# MainBoard.net
KiCad netlist of a schematic drawn in Altium Designer
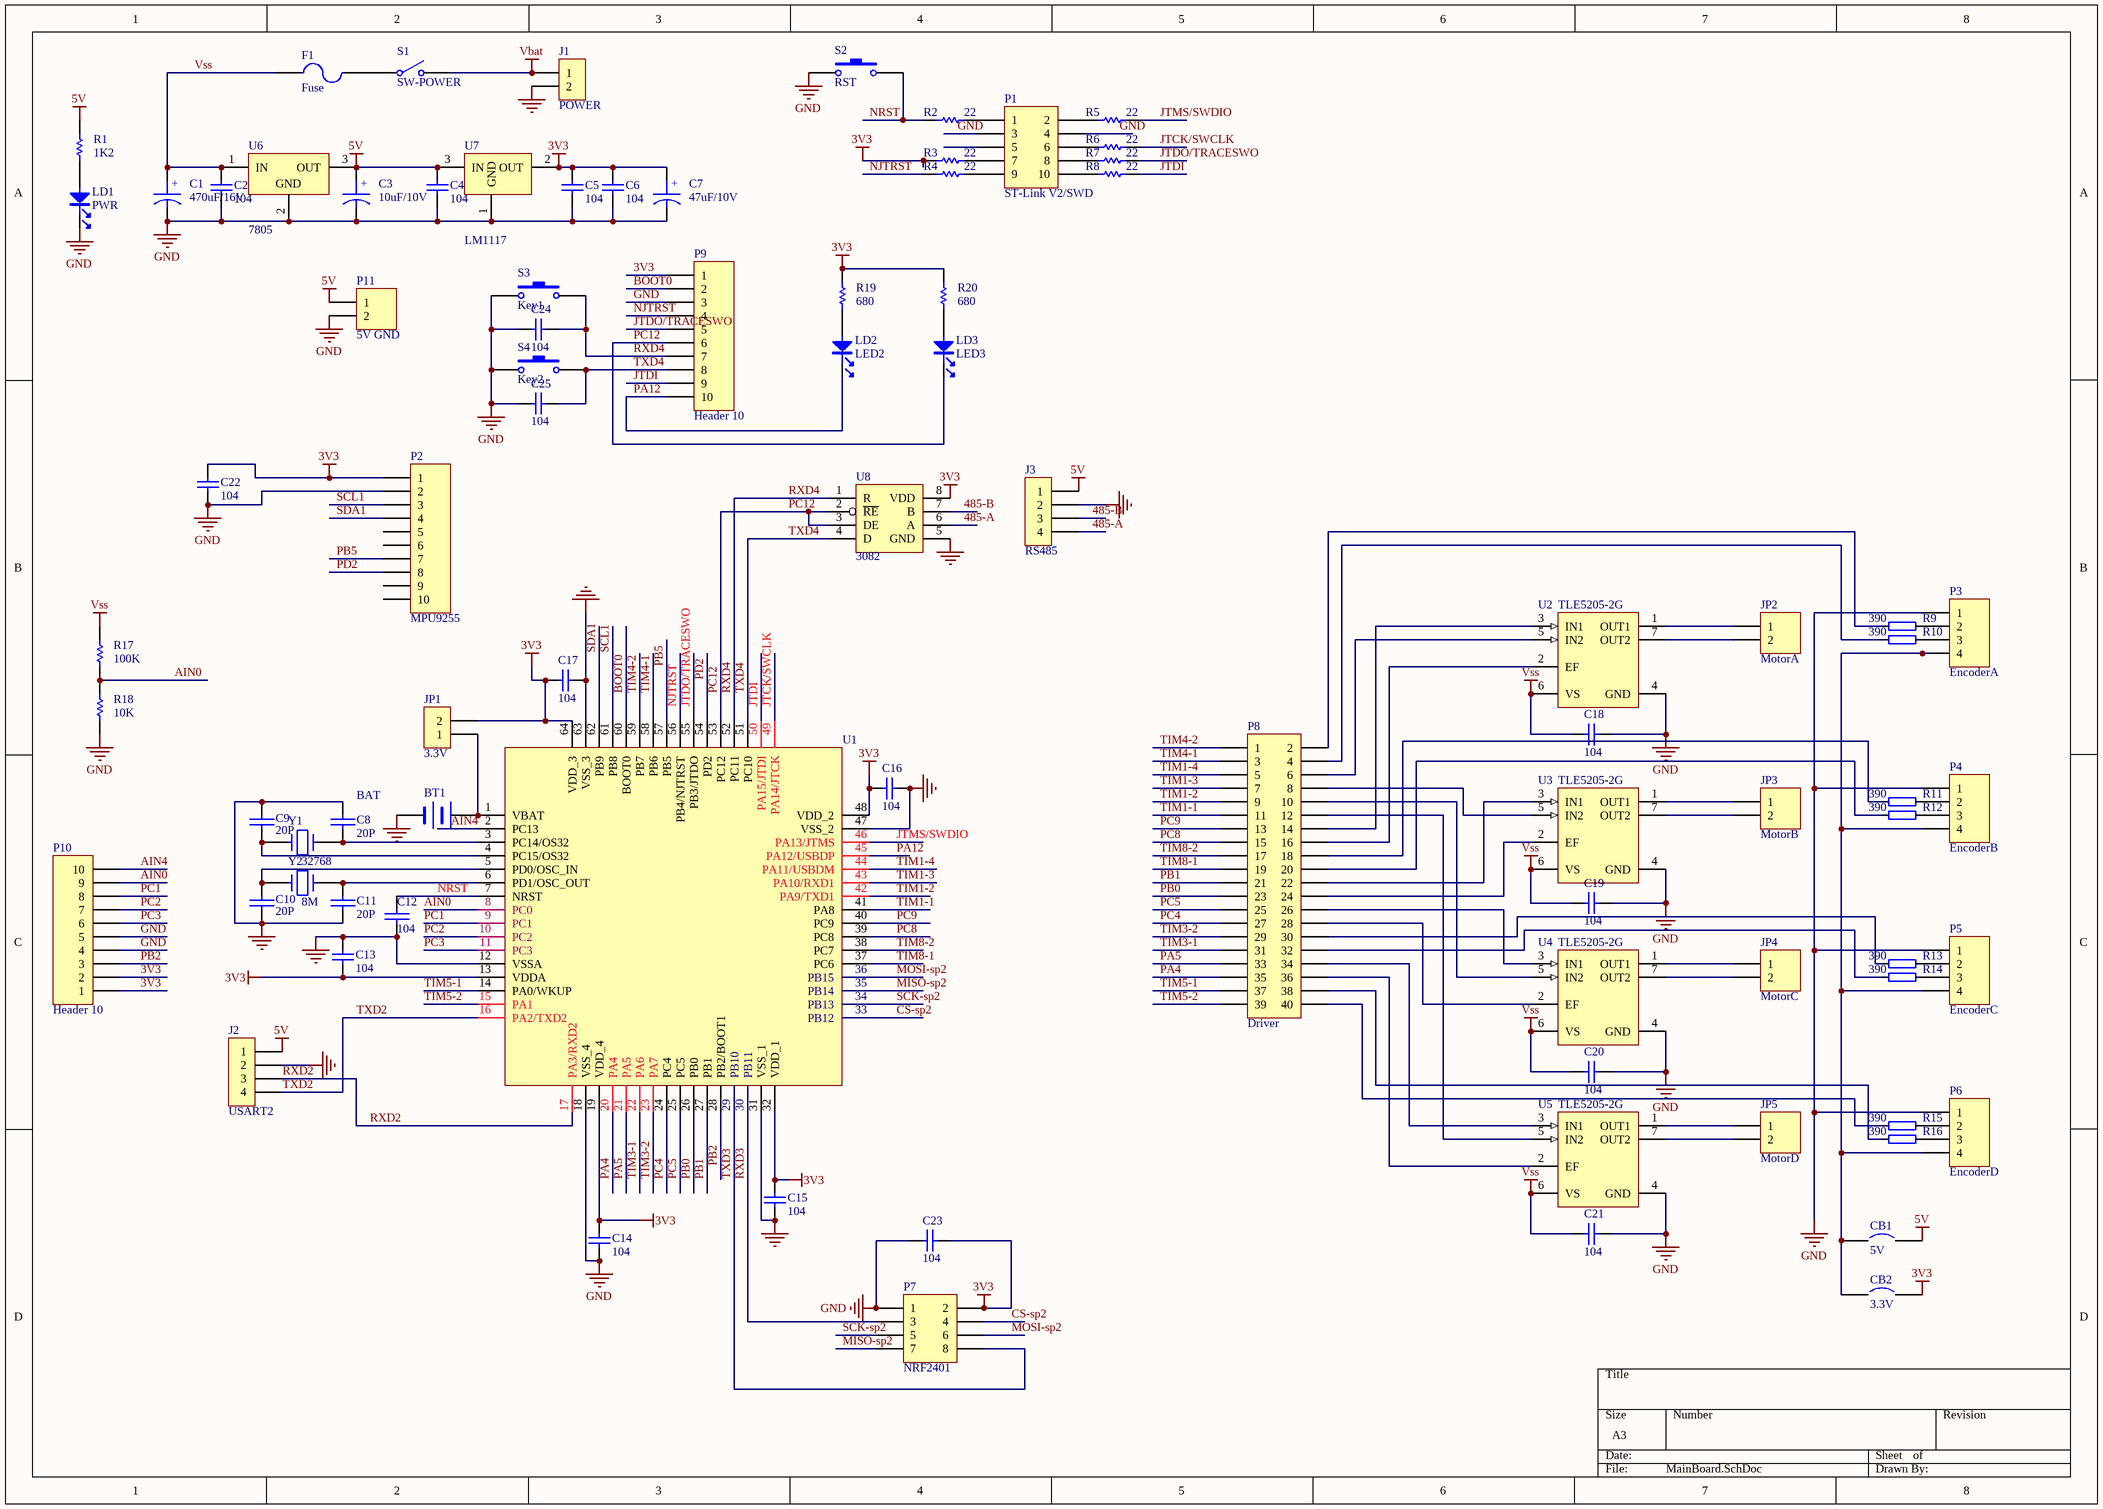
[diagram p0: MainBoard.SchDoc]

(export (version "E")
  (design (tool "Eeschema 10.0.6"))
  (components
    (comp (ref "BT1")
      (value "BAT")
      (footprint "SIP2 - duplicate")
      (description "Battery")
      (libsource (lib "*") (part "BATTERY"))
    )
    (comp (ref "C1") (value "470uF/16V") (footprint "RB2") (libsource (lib "SmartHome") (part "CAP POL")))
    (comp (ref "C2")
      (value "104")
      (description "Capacitor")
      (fields (field (name "Comment") "Cap") (field (name "PUBLISHER") "Altium Limited"))
      (libsource (lib "Miscellaneous Devices") (part "Cap"))
    )
    (comp (ref "C3") (value "10uF/10V") (footprint "RB2") (libsource (lib "SmartHome") (part "CAP POL")))
    (comp (ref "C4")
      (value "104")
      (description "Capacitor")
      (fields (field (name "Comment") "Cap") (field (name "PUBLISHER") "Altium Limited"))
      (libsource (lib "Miscellaneous Devices") (part "Cap"))
    )
    (comp (ref "C5")
      (value "104")
      (description "Capacitor")
      (fields (field (name "Comment") "Cap") (field (name "PUBLISHER") "Altium Limited"))
      (libsource (lib "Miscellaneous Devices") (part "Cap"))
    )
    (comp (ref "C6")
      (value "104")
      (description "Capacitor")
      (fields (field (name "Comment") "Cap") (field (name "PUBLISHER") "Altium Limited"))
      (libsource (lib "Miscellaneous Devices") (part "Cap"))
    )
    (comp (ref "C7") (value "47uF/10V") (footprint "RB2") (libsource (lib "SmartHome") (part "CAP POL")))
    (comp (ref "C8")
      (value "20P")
      (footprint "0603")
      (description "Capacitor")
      (libsource (lib "*") (part "CAP"))
    )
    (comp (ref "C9")
      (value "20P")
      (footprint "0603")
      (description "Capacitor")
      (libsource (lib "*") (part "CAP"))
    )
    (comp (ref "C10")
      (value "20P")
      (footprint "0603")
      (description "Capacitor")
      (libsource (lib "*") (part "CAP"))
    )
    (comp (ref "C11")
      (value "20P")
      (footprint "0603")
      (description "Capacitor")
      (libsource (lib "*") (part "CAP"))
    )
    (comp (ref "C12")
      (value "104")
      (footprint "0603")
      (description "Capacitor")
      (libsource (lib "*") (part "CAP"))
    )
    (comp (ref "C13")
      (value "104")
      (description "Capacitor")
      (fields (field (name "Comment") "Cap") (field (name "PUBLISHER") "Altium Limited"))
      (libsource (lib "Miscellaneous Devices") (part "Cap"))
    )
    (comp (ref "C14")
      (value "104")
      (description "Capacitor")
      (fields (field (name "Comment") "Cap") (field (name "PUBLISHER") "Altium Limited"))
      (libsource (lib "Miscellaneous Devices") (part "Cap"))
    )
    (comp (ref "C15")
      (value "104")
      (description "Capacitor")
      (fields (field (name "Comment") "Cap") (field (name "PUBLISHER") "Altium Limited"))
      (libsource (lib "Miscellaneous Devices") (part "Cap"))
    )
    (comp (ref "C16")
      (value "104")
      (description "Capacitor")
      (fields (field (name "Comment") "Cap") (field (name "PUBLISHER") "Altium Limited"))
      (libsource (lib "Miscellaneous Devices") (part "Cap"))
    )
    (comp (ref "C17")
      (value "104")
      (description "Capacitor")
      (fields (field (name "Comment") "Cap") (field (name "PUBLISHER") "Altium Limited"))
      (libsource (lib "Miscellaneous Devices") (part "Cap"))
    )
    (comp (ref "C18")
      (value "104")
      (description "Capacitor")
      (fields (field (name "Comment") "Cap") (field (name "PUBLISHER") "Altium Limited"))
      (libsource (lib "Miscellaneous Devices") (part "Cap"))
    )
    (comp (ref "C19")
      (value "104")
      (description "Capacitor")
      (fields (field (name "Comment") "Cap") (field (name "PUBLISHER") "Altium Limited"))
      (libsource (lib "Miscellaneous Devices") (part "Cap"))
    )
    (comp (ref "C20")
      (value "104")
      (description "Capacitor")
      (fields (field (name "Comment") "Cap") (field (name "PUBLISHER") "Altium Limited"))
      (libsource (lib "Miscellaneous Devices") (part "Cap"))
    )
    (comp (ref "C21")
      (value "104")
      (description "Capacitor")
      (fields (field (name "Comment") "Cap") (field (name "PUBLISHER") "Altium Limited"))
      (libsource (lib "Miscellaneous Devices") (part "Cap"))
    )
    (comp (ref "C22")
      (value "104")
      (description "Capacitor")
      (fields (field (name "Comment") "Cap") (field (name "PUBLISHER") "Altium Limited"))
      (libsource (lib "Miscellaneous Devices") (part "Cap"))
    )
    (comp (ref "C23")
      (value "104")
      (description "Capacitor")
      (fields (field (name "Comment") "Cap") (field (name "PUBLISHER") "Altium Limited"))
      (libsource (lib "Miscellaneous Devices") (part "Cap"))
    )
    (comp (ref "C24")
      (value "104")
      (description "Capacitor")
      (fields (field (name "Comment") "Cap") (field (name "PUBLISHER") "Altium Limited"))
      (libsource (lib "Miscellaneous Devices") (part "Cap"))
    )
    (comp (ref "C25")
      (value "104")
      (description "Capacitor")
      (fields (field (name "Comment") "Cap") (field (name "PUBLISHER") "Altium Limited"))
      (libsource (lib "Miscellaneous Devices") (part "Cap"))
    )
    (comp (ref "CB1")
      (value "5V")
      (footprint "SIP2 - duplicate")
      (description "Circuit Breaker")
      (fields (field (name "PUBLISHER") "Altium Limited"))
      (libsource (lib "Miscellaneous Devices") (part "Circuit Breaker"))
    )
    (comp (ref "CB2")
      (value "3.3V")
      (footprint "SIP2 - duplicate")
      (description "Circuit Breaker")
      (fields (field (name "PUBLISHER") "Altium Limited"))
      (libsource (lib "Miscellaneous Devices") (part "Circuit Breaker"))
    )
    (comp (ref "F1")
      (value "Fuse")
      (footprint "1808Shell")
      (fields (field (name "PUBLISHER") "Altium Limited"))
      (libsource (lib "Miscellaneous Devices") (part "Fuse 2"))
    )
    (comp (ref "J1")
      (value "POWER")
      (footprint "SIP2-150")
      (description "Connector")
      (libsource (lib "*") (part "CON2"))
    )
    (comp (ref "J2")
      (value "USART2")
      (footprint "sip4")
      (description "Connector")
      (libsource (lib "*") (part "CON4"))
    )
    (comp (ref "J3")
      (value "RS485")
      (footprint "sip4")
      (description "Connector")
      (libsource (lib "*") (part "CON4"))
    )
    (comp (ref "JP1")
      (value "3.3V")
      (footprint "SIP2 - duplicate")
      (description "Connector")
      (libsource (lib "") (part "CON2_1"))
    )
    (comp (ref "JP2")
      (value "MotorA")
      (footprint "SIP2-150")
      (description "Header, 2-Pin")
      (fields (field (name "PUBLISHER") "Altium Limited"))
      (libsource (lib "Miscellaneous Connectors") (part "Header 2"))
    )
    (comp (ref "JP3")
      (value "MotorB")
      (footprint "SIP2-150")
      (description "Header, 2-Pin")
      (fields (field (name "PUBLISHER") "Altium Limited"))
      (libsource (lib "Miscellaneous Connectors") (part "Header 2"))
    )
    (comp (ref "JP4")
      (value "MotorC")
      (footprint "SIP2-150")
      (description "Header, 2-Pin")
      (fields (field (name "PUBLISHER") "Altium Limited"))
      (libsource (lib "Miscellaneous Connectors") (part "Header 2"))
    )
    (comp (ref "JP5")
      (value "MotorD")
      (footprint "SIP2-150")
      (description "Header, 2-Pin")
      (fields (field (name "PUBLISHER") "Altium Limited"))
      (libsource (lib "Miscellaneous Connectors") (part "Header 2"))
    )
    (comp (ref "LD1") (value "PWR") (footprint "0603") (libsource (lib "MB963_1") (part "PHOTO")))
    (comp (ref "LD2") (value "LED2") (footprint "0603") (libsource (lib "MB963_1") (part "PHOTO")))
    (comp (ref "LD3") (value "LED3") (footprint "0603") (libsource (lib "MB963_1") (part "PHOTO")))
    (comp (ref "P1")
      (value "ST-Link V2/SWD")
      (footprint "HDR2X5")
      (description "Header, 5-Pin, Dual row")
      (fields (field (name "PUBLISHER") "Altium Limited"))
      (libsource (lib "Miscellaneous Connectors") (part "Header 5X2"))
    )
    (comp (ref "P2")
      (value "MPU9255")
      (footprint "HDR1X10")
      (description "Header, 10-Pin")
      (fields (field (name "PUBLISHER") "Altium Limited"))
      (libsource (lib "Miscellaneous Connectors") (part "Header 10"))
    )
    (comp (ref "P3")
      (value "EncoderA")
      (footprint "HDR1X4")
      (description "Header, 4-Pin")
      (fields (field (name "PUBLISHER") "Altium Limited"))
      (libsource (lib "Miscellaneous Connectors") (part "Header 4"))
    )
    (comp (ref "P4")
      (value "EncoderB")
      (footprint "HDR1X4")
      (description "Header, 4-Pin")
      (fields (field (name "PUBLISHER") "Altium Limited"))
      (libsource (lib "Miscellaneous Connectors") (part "Header 4"))
    )
    (comp (ref "P5")
      (value "EncoderC")
      (footprint "HDR1X4")
      (description "Header, 4-Pin")
      (fields (field (name "PUBLISHER") "Altium Limited"))
      (libsource (lib "Miscellaneous Connectors") (part "Header 4"))
    )
    (comp (ref "P6")
      (value "EncoderD")
      (footprint "HDR1X4")
      (description "Header, 4-Pin")
      (fields (field (name "PUBLISHER") "Altium Limited"))
      (libsource (lib "Miscellaneous Connectors") (part "Header 4"))
    )
    (comp (ref "P7")
      (value "NRF2401")
      (footprint "HDR2X4")
      (description "Header, 4-Pin, Dual row")
      (fields (field (name "PUBLISHER") "Altium Limited"))
      (libsource (lib "Miscellaneous Connectors") (part "Header 4X2"))
    )
    (comp (ref "P8")
      (value "Driver")
      (footprint "HDR2X20")
      (description "Header, 20-Pin, Dual row")
      (fields (field (name "PUBLISHER") "Altium Limited"))
      (libsource (lib "Miscellaneous Connectors") (part "Header 20X2"))
    )
    (comp (ref "P9")
      (value "Header 10")
      (footprint "HDR1X10")
      (description "Header, 10-Pin")
      (fields (field (name "PUBLISHER") "Altium Limited"))
      (libsource (lib "Miscellaneous Connectors") (part "Header 10"))
    )
    (comp (ref "P10")
      (value "Header 10")
      (footprint "HDR1X10")
      (description "Header, 10-Pin")
      (fields (field (name "PUBLISHER") "Altium Limited"))
      (libsource (lib "") (part "Header 10_1"))
    )
    (comp (ref "P11")
      (value "5V GND")
      (footprint "HDR1X2")
      (description "Header, 2-Pin")
      (fields (field (name "PUBLISHER") "Altium Limited"))
      (libsource (lib "Miscellaneous Connectors") (part "Header 2"))
    )
    (comp (ref "R1")
      (value "1K2")
      (footprint "0603")
      (description "Resistor 0402 / 0603 / 0805")
      (libsource (lib "MCD_TOOLS") (part "Resistor_ST"))
    )
    (comp (ref "R2")
      (value "22")
      (footprint "0603")
      (description "Resistor 0402 / 0603 / 0805")
      (libsource (lib "Miscellaneous Devices") (part "Res1"))
    )
    (comp (ref "R3")
      (value "22")
      (footprint "0603")
      (description "Resistor 0402 / 0603 / 0805")
      (libsource (lib "Miscellaneous Devices") (part "Res1"))
    )
    (comp (ref "R4")
      (value "22")
      (footprint "0603")
      (description "Resistor 0402 / 0603 / 0805")
      (libsource (lib "Miscellaneous Devices") (part "Res1"))
    )
    (comp (ref "R5")
      (value "22")
      (footprint "0603")
      (description "Resistor 0402 / 0603 / 0805")
      (libsource (lib "Miscellaneous Devices") (part "Res1"))
    )
    (comp (ref "R6")
      (value "22")
      (footprint "0603")
      (description "Resistor 0402 / 0603 / 0805")
      (libsource (lib "Miscellaneous Devices") (part "Res1"))
    )
    (comp (ref "R7")
      (value "22")
      (footprint "0603")
      (description "Resistor 0402 / 0603 / 0805")
      (libsource (lib "Miscellaneous Devices") (part "Res1"))
    )
    (comp (ref "R8")
      (value "22")
      (footprint "0603")
      (description "Resistor 0402 / 0603 / 0805")
      (libsource (lib "Miscellaneous Devices") (part "Res1"))
    )
    (comp (ref "R9") (value "390") (footprint "0603") (libsource (lib "电阻") (part "RES")))
    (comp (ref "R10") (value "390") (footprint "0603") (libsource (lib "电阻") (part "RES")))
    (comp (ref "R11") (value "390") (footprint "0603") (libsource (lib "电阻") (part "RES")))
    (comp (ref "R12") (value "390") (footprint "0603") (libsource (lib "电阻") (part "RES")))
    (comp (ref "R13") (value "390") (footprint "0603") (libsource (lib "电阻") (part "RES")))
    (comp (ref "R14") (value "390") (footprint "0603") (libsource (lib "电阻") (part "RES")))
    (comp (ref "R15") (value "390") (footprint "0603") (libsource (lib "电阻") (part "RES")))
    (comp (ref "R16") (value "390") (footprint "0603") (libsource (lib "电阻") (part "RES")))
    (comp (ref "R17")
      (value "100K")
      (footprint "0603")
      (description "Resistor 0402 / 0603 / 0805")
      (libsource (lib "MCD_TOOLS") (part "Resistor_ST"))
    )
    (comp (ref "R18")
      (value "10K")
      (footprint "0603")
      (description "Resistor 0402 / 0603 / 0805")
      (libsource (lib "MCD_TOOLS") (part "Resistor_ST"))
    )
    (comp (ref "R19")
      (value "680")
      (footprint "0603")
      (description "Resistor 0402 / 0603 / 0805")
      (libsource (lib "MCD_TOOLS") (part "Resistor_ST"))
    )
    (comp (ref "R20")
      (value "680")
      (footprint "0603")
      (description "Resistor 0402 / 0603 / 0805")
      (libsource (lib "MCD_TOOLS") (part "Resistor_ST"))
    )
    (comp (ref "S1")
      (value "SW-POWER")
      (footprint "SPST-2")
      (description "Single-Pole, Single-Throw Switch")
      (fields (field (name "PUBLISHER") "Altium Limited"))
      (libsource (lib "Miscellaneous Devices") (part "SW-SPST"))
    )
    (comp (ref "S2")
      (value "RST")
      (footprint "key2")
      (description "Switch")
      (fields (field (name "PUBLISHER") "Altium Limited"))
      (libsource (lib "Miscellaneous Devices") (part "SW-PB"))
    )
    (comp (ref "S3")
      (value "Key1")
      (footprint "key2")
      (description "Switch")
      (fields (field (name "PUBLISHER") "Altium Limited"))
      (libsource (lib "Miscellaneous Devices") (part "SW-PB"))
    )
    (comp (ref "S4")
      (value "Key2")
      (footprint "key2")
      (description "Switch")
      (fields (field (name "PUBLISHER") "Altium Limited"))
      (libsource (lib "Miscellaneous Devices") (part "SW-PB"))
    )
    (comp (ref "U1") (value "~") (footprint "quad64") (libsource (lib "*") (part "STM32F103R8")))
    (comp (ref "U2")
      (value "TLE5205-2G")
      (footprint "INF-PG-TO263-7-1_L")
      (description "5 A H-Bridge for DC-Motor Applications, 6 to 40 V, 220 mOhm RDS(on), PG-TO263-7-1, Reel, Green")
      (fields (field (name "MANUFACTURER") "Infineon"))
      (libsource (lib "TLE5205-2G") (part "TLE5205-2G"))
    )
    (comp (ref "U3")
      (value "TLE5205-2G")
      (footprint "INF-PG-TO263-7-1_L")
      (description "5 A H-Bridge for DC-Motor Applications, 6 to 40 V, 220 mOhm RDS(on), PG-TO263-7-1, Reel, Green")
      (fields (field (name "MANUFACTURER") "Infineon"))
      (libsource (lib "TLE5205-2G") (part "TLE5205-2G"))
    )
    (comp (ref "U4")
      (value "TLE5205-2G")
      (footprint "INF-PG-TO263-7-1_L")
      (description "5 A H-Bridge for DC-Motor Applications, 6 to 40 V, 220 mOhm RDS(on), PG-TO263-7-1, Reel, Green")
      (fields (field (name "MANUFACTURER") "Infineon"))
      (libsource (lib "TLE5205-2G") (part "TLE5205-2G"))
    )
    (comp (ref "U5")
      (value "TLE5205-2G")
      (footprint "INF-PG-TO263-7-1_L")
      (description "5 A H-Bridge for DC-Motor Applications, 6 to 40 V, 220 mOhm RDS(on), PG-TO263-7-1, Reel, Green")
      (fields (field (name "MANUFACTURER") "Infineon"))
      (libsource (lib "TLE5205-2G") (part "TLE5205-2G"))
    )
    (comp (ref "U6")
      (value "7805")
      (footprint "ktt")
      (description "3-Terminal Positive Regulator")
      (fields (field (name "PUBLISHER") "Altium Limited"))
      (libsource (lib "TI Power Mgt Voltage Regulator") (part "LM330KC"))
    )
    (comp (ref "U7") (value "LM1117") (footprint "SPP3") (libsource (lib "*") (part "LM1117")))
    (comp (ref "U8") (value "3082") (footprint "so-8") (libsource (lib "*") (part "75176")))
    (comp (ref "Y1")
      (value "32768")
      (footprint "sip2")
      (description "Crystal")
      (libsource (lib "*") (part "CRYSTAL"))
    )
    (comp (ref "Y2")
      (value "8M")
      (footprint "XTAL1")
      (description "Crystal")
      (libsource (lib "*") (part "CRYSTAL"))
    )
  )
  (nets
    (net (code "1") (name "/485-A") (class "Default")
      (node (ref "J3") (pin "4") (pinfunction "4_4") (pintype "passive"))
      (node (ref "U8") (pin "6") (pinfunction "A_6") (pintype "passive"))
    )
    (net (code "2") (name "/485-B") (class "Default")
      (node (ref "J3") (pin "3") (pinfunction "3_3") (pintype "passive"))
      (node (ref "U8") (pin "7") (pinfunction "B_7") (pintype "passive"))
    )
    (net (code "3") (name "/AIN0") (class "Default")
      (node (ref "P10") (pin "9") (pinfunction "9_9") (pintype "passive"))
      (node (ref "R17") (pin "1") (pinfunction "1_1") (pintype "passive"))
      (node (ref "R18") (pin "2") (pinfunction "2_2") (pintype "passive"))
      (node (ref "U1") (pin "8") (pinfunction "PC0_8") (pintype "passive"))
    )
    (net (code "4") (name "/AIN4") (class "Default")
      (node (ref "P10") (pin "10") (pinfunction "10_10") (pintype "passive"))
      (node (ref "U1") (pin "2") (pinfunction "PC13_2") (pintype "passive"))
    )
    (net (code "5") (name "/BOOT0") (class "Default")
      (node (ref "P9") (pin "2") (pinfunction "2_2") (pintype "passive"))
      (node (ref "U1") (pin "60") (pinfunction "BOOT0_60") (pintype "passive"))
    )
    (net (code "6") (name "/CS-sp2") (class "Default")
      (node (ref "P7") (pin "4") (pinfunction "4_4") (pintype "passive"))
      (node (ref "U1") (pin "33") (pinfunction "PB12_33") (pintype "passive"))
    )
    (net (code "7") (name "/JTCK{slash}SWCLK") (class "Default")
      (node (ref "R6") (pin "2") (pinfunction "2_2") (pintype "passive"))
      (node (ref "U1") (pin "49") (pinfunction "PA14/JTCK_49") (pintype "passive"))
    )
    (net (code "8") (name "/JTDI") (class "Default")
      (node (ref "P9") (pin "9") (pinfunction "9_9") (pintype "passive"))
      (node (ref "R8") (pin "2") (pinfunction "2_2") (pintype "passive"))
      (node (ref "U1") (pin "50") (pinfunction "PA15/JTDI_50") (pintype "passive"))
    )
    (net (code "9") (name "/JTDO{slash}TRACESWO") (class "Default")
      (node (ref "P9") (pin "5") (pinfunction "5_5") (pintype "passive"))
      (node (ref "R7") (pin "2") (pinfunction "2_2") (pintype "passive"))
      (node (ref "U1") (pin "55") (pinfunction "PB3/JTDO_55") (pintype "passive"))
    )
    (net (code "10") (name "/JTMS{slash}SWDIO") (class "Default")
      (node (ref "R5") (pin "2") (pinfunction "2_2") (pintype "passive"))
      (node (ref "U1") (pin "46") (pinfunction "PA13/JTMS_46") (pintype "passive"))
    )
    (net (code "11") (name "/MISO-sp2") (class "Default")
      (node (ref "P7") (pin "7") (pinfunction "7_7") (pintype "passive"))
      (node (ref "U1") (pin "35") (pinfunction "PB14_35") (pintype "passive"))
    )
    (net (code "12") (name "/MOSI-sp2") (class "Default")
      (node (ref "P7") (pin "6") (pinfunction "6_6") (pintype "passive"))
      (node (ref "U1") (pin "36") (pinfunction "PB15_36") (pintype "passive"))
    )
    (net (code "13") (name "/NJTRST") (class "Default")
      (node (ref "P9") (pin "4") (pinfunction "4_4") (pintype "passive"))
      (node (ref "R4") (pin "1") (pinfunction "1_1") (pintype "passive"))
      (node (ref "U1") (pin "56") (pinfunction "PB4/NJTRST_56") (pintype "passive"))
    )
    (net (code "14") (name "/NRST") (class "Default")
      (node (ref "C12") (pin "1") (pinfunction "1_1") (pintype "passive"))
      (node (ref "R2") (pin "1") (pinfunction "1_1") (pintype "passive"))
      (node (ref "S2") (pin "2") (pinfunction "2_2") (pintype "passive"))
      (node (ref "U1") (pin "7") (pinfunction "NRST_7") (pintype "passive"))
    )
    (net (code "15") (name "/PA4") (class "Default")
      (node (ref "P8") (pin "35") (pinfunction "35_35") (pintype "passive"))
      (node (ref "U1") (pin "20") (pinfunction "PA4_20") (pintype "passive"))
    )
    (net (code "16") (name "/PA5") (class "Default")
      (node (ref "P8") (pin "33") (pinfunction "33_33") (pintype "passive"))
      (node (ref "U1") (pin "21") (pinfunction "PA5_21") (pintype "passive"))
    )
    (net (code "17") (name "/PA12") (class "Default")
      (node (ref "LD2") (pin "2") (pintype "passive"))
      (node (ref "P9") (pin "10") (pinfunction "10_10") (pintype "passive"))
      (node (ref "U1") (pin "45") (pinfunction "PA12/USBDP_45") (pintype "passive"))
    )
    (net (code "18") (name "/PB0") (class "Default")
      (node (ref "P8") (pin "23") (pinfunction "23_23") (pintype "passive"))
      (node (ref "U1") (pin "26") (pinfunction "PB0_26") (pintype "passive"))
    )
    (net (code "19") (name "/PB1") (class "Default")
      (node (ref "P8") (pin "21") (pinfunction "21_21") (pintype "passive"))
      (node (ref "U1") (pin "27") (pinfunction "PB1_27") (pintype "passive"))
    )
    (net (code "20") (name "/PB2") (class "Default")
      (node (ref "P10") (pin "3") (pinfunction "3_3") (pintype "passive"))
      (node (ref "U1") (pin "28") (pinfunction "PB2/BOOT1_28") (pintype "passive"))
    )
    (net (code "21") (name "/PB5") (class "Default")
      (node (ref "P2") (pin "7") (pinfunction "7_7") (pintype "passive"))
      (node (ref "U1") (pin "57") (pinfunction "PB5_57") (pintype "passive"))
    )
    (net (code "22") (name "/PC1") (class "Default")
      (node (ref "P10") (pin "8") (pinfunction "8_8") (pintype "passive"))
      (node (ref "U1") (pin "9") (pinfunction "PC1_9") (pintype "passive"))
    )
    (net (code "23") (name "/PC2") (class "Default")
      (node (ref "P10") (pin "7") (pinfunction "7_7") (pintype "passive"))
      (node (ref "U1") (pin "10") (pinfunction "PC2_10") (pintype "passive"))
    )
    (net (code "24") (name "/PC3") (class "Default")
      (node (ref "P10") (pin "6") (pinfunction "6_6") (pintype "passive"))
      (node (ref "U1") (pin "11") (pinfunction "PC3_11") (pintype "passive"))
    )
    (net (code "25") (name "/PC4") (class "Default")
      (node (ref "P8") (pin "27") (pinfunction "27_27") (pintype "passive"))
      (node (ref "U1") (pin "24") (pinfunction "PC4_24") (pintype "passive"))
    )
    (net (code "26") (name "/PC5") (class "Default")
      (node (ref "P8") (pin "25") (pinfunction "25_25") (pintype "passive"))
      (node (ref "U1") (pin "25") (pinfunction "PC5_25") (pintype "passive"))
    )
    (net (code "27") (name "/PC8") (class "Default")
      (node (ref "P8") (pin "15") (pinfunction "15_15") (pintype "passive"))
      (node (ref "U1") (pin "39") (pinfunction "PC8_39") (pintype "passive"))
    )
    (net (code "28") (name "/PC9") (class "Default")
      (node (ref "P8") (pin "13") (pinfunction "13_13") (pintype "passive"))
      (node (ref "U1") (pin "40") (pinfunction "PC9_40") (pintype "passive"))
    )
    (net (code "29") (name "/PC12") (class "Default")
      (node (ref "LD3") (pin "2") (pintype "passive"))
      (node (ref "P9") (pin "6") (pinfunction "6_6") (pintype "passive"))
      (node (ref "U1") (pin "53") (pinfunction "PC12_53") (pintype "passive"))
      (node (ref "U8") (pin "2") (pinfunction "~{RE}_2") (pintype "passive"))
      (node (ref "U8") (pin "3") (pinfunction "DE_3") (pintype "passive"))
    )
    (net (code "30") (name "/PD2") (class "Default")
      (node (ref "P2") (pin "8") (pinfunction "8_8") (pintype "passive"))
      (node (ref "U1") (pin "54") (pinfunction "PD2_54") (pintype "passive"))
    )
    (net (code "31") (name "/RXD2") (class "Default")
      (node (ref "J2") (pin "3") (pinfunction "3_3") (pintype "passive"))
      (node (ref "U1") (pin "17") (pinfunction "PA3/RXD2_17") (pintype "passive"))
    )
    (net (code "32") (name "/RXD3") (class "Default")
      (node (ref "P7") (pin "3") (pinfunction "3_3") (pintype "passive"))
      (node (ref "U1") (pin "30") (pinfunction "PB11_30") (pintype "passive"))
    )
    (net (code "33") (name "/RXD4") (class "Default")
      (node (ref "C24") (pin "2") (pinfunction "2_2") (pintype "passive"))
      (node (ref "P9") (pin "7") (pinfunction "7_7") (pintype "passive"))
      (node (ref "S3") (pin "2") (pinfunction "2_2") (pintype "passive"))
      (node (ref "U1") (pin "52") (pinfunction "PC11_52") (pintype "passive"))
      (node (ref "U8") (pin "1") (pinfunction "R_1") (pintype "passive"))
    )
    (net (code "34") (name "/SCK-sp2") (class "Default")
      (node (ref "P7") (pin "5") (pinfunction "5_5") (pintype "passive"))
      (node (ref "U1") (pin "34") (pinfunction "PB13_34") (pintype "passive"))
    )
    (net (code "35") (name "/SCL1") (class "Default")
      (node (ref "P2") (pin "3") (pinfunction "3_3") (pintype "passive"))
      (node (ref "U1") (pin "61") (pinfunction "PB8_61") (pintype "passive"))
    )
    (net (code "36") (name "/SDA1") (class "Default")
      (node (ref "P2") (pin "4") (pinfunction "4_4") (pintype "passive"))
      (node (ref "U1") (pin "62") (pinfunction "PB9_62") (pintype "passive"))
    )
    (net (code "37") (name "/TIM1-1") (class "Default")
      (node (ref "P8") (pin "11") (pinfunction "11_11") (pintype "passive"))
      (node (ref "U1") (pin "41") (pinfunction "PA8_41") (pintype "passive"))
    )
    (net (code "38") (name "/TIM1-2") (class "Default")
      (node (ref "P8") (pin "9") (pinfunction "9_9") (pintype "passive"))
      (node (ref "U1") (pin "42") (pinfunction "PA9/TXD1_42") (pintype "passive"))
    )
    (net (code "39") (name "/TIM1-3") (class "Default")
      (node (ref "P8") (pin "7") (pinfunction "7_7") (pintype "passive"))
      (node (ref "U1") (pin "43") (pinfunction "PA10/RXD1_43") (pintype "passive"))
    )
    (net (code "40") (name "/TIM1-4") (class "Default")
      (node (ref "P8") (pin "5") (pinfunction "5_5") (pintype "passive"))
      (node (ref "U1") (pin "44") (pinfunction "PA11/USBDM_44") (pintype "passive"))
    )
    (net (code "41") (name "/TIM3-1") (class "Default")
      (node (ref "P8") (pin "31") (pinfunction "31_31") (pintype "passive"))
      (node (ref "U1") (pin "22") (pinfunction "PA6_22") (pintype "passive"))
    )
    (net (code "42") (name "/TIM3-2") (class "Default")
      (node (ref "P8") (pin "29") (pinfunction "29_29") (pintype "passive"))
      (node (ref "U1") (pin "23") (pinfunction "PA7_23") (pintype "passive"))
    )
    (net (code "43") (name "/TIM4-1") (class "Default")
      (node (ref "P8") (pin "3") (pinfunction "3_3") (pintype "passive"))
      (node (ref "U1") (pin "58") (pinfunction "PB6_58") (pintype "passive"))
    )
    (net (code "44") (name "/TIM4-2") (class "Default")
      (node (ref "P8") (pin "1") (pinfunction "1_1") (pintype "passive"))
      (node (ref "U1") (pin "59") (pinfunction "PB7_59") (pintype "passive"))
    )
    (net (code "45") (name "/TIM5-1") (class "Default")
      (node (ref "P8") (pin "37") (pinfunction "37_37") (pintype "passive"))
      (node (ref "U1") (pin "14") (pinfunction "PA0/WKUP_14") (pintype "passive"))
    )
    (net (code "46") (name "/TIM5-2") (class "Default")
      (node (ref "P8") (pin "39") (pinfunction "39_39") (pintype "passive"))
      (node (ref "U1") (pin "15") (pinfunction "PA1_15") (pintype "passive"))
    )
    (net (code "47") (name "/TIM8-1") (class "Default")
      (node (ref "P8") (pin "19") (pinfunction "19_19") (pintype "passive"))
      (node (ref "U1") (pin "37") (pinfunction "PC6_37") (pintype "passive"))
    )
    (net (code "48") (name "/TIM8-2") (class "Default")
      (node (ref "P8") (pin "17") (pinfunction "17_17") (pintype "passive"))
      (node (ref "U1") (pin "38") (pinfunction "PC7_38") (pintype "passive"))
    )
    (net (code "49") (name "/TXD2") (class "Default")
      (node (ref "J2") (pin "4") (pinfunction "4_4") (pintype "passive"))
      (node (ref "U1") (pin "16") (pinfunction "PA2/TXD2_16") (pintype "passive"))
    )
    (net (code "50") (name "/TXD3") (class "Default")
      (node (ref "P7") (pin "8") (pinfunction "8_8") (pintype "passive"))
      (node (ref "U1") (pin "29") (pinfunction "PB10_29") (pintype "passive"))
    )
    (net (code "51") (name "/TXD4") (class "Default")
      (node (ref "C25") (pin "2") (pinfunction "2_2") (pintype "passive"))
      (node (ref "P9") (pin "8") (pinfunction "8_8") (pintype "passive"))
      (node (ref "S4") (pin "2") (pinfunction "2_2") (pintype "passive"))
      (node (ref "U1") (pin "51") (pinfunction "PC10_51") (pintype "passive"))
      (node (ref "U8") (pin "4") (pinfunction "D_4") (pintype "passive"))
    )
    (net (code "52") (name "3V3") (class "Default")
      (node (ref "C13") (pin "1") (pinfunction "1_1") (pintype "passive"))
      (node (ref "C14") (pin "2") (pinfunction "2_2") (pintype "passive"))
      (node (ref "C15") (pin "2") (pinfunction "2_2") (pintype "passive"))
      (node (ref "C16") (pin "1") (pinfunction "1_1") (pintype "passive"))
      (node (ref "C17") (pin "2") (pinfunction "2_2") (pintype "passive"))
      (node (ref "C22") (pin "1") (pinfunction "1_1") (pintype "passive"))
      (node (ref "C23") (pin "1") (pinfunction "1_1") (pintype "passive"))
      (node (ref "C5") (pin "2") (pinfunction "2_2") (pintype "passive"))
      (node (ref "C6") (pin "2") (pinfunction "2_2") (pintype "passive"))
      (node (ref "C7") (pin "1") (pinfunction "1_1") (pintype "passive"))
      (node (ref "CB2") (pin "2") (pinfunction "2_2") (pintype "passive"))
      (node (ref "JP1") (pin "2") (pinfunction "2_2") (pintype "passive"))
      (node (ref "P10") (pin "1") (pinfunction "1_1") (pintype "passive"))
      (node (ref "P10") (pin "2") (pinfunction "2_2") (pintype "passive"))
      (node (ref "P2") (pin "1") (pinfunction "1_1") (pintype "passive"))
      (node (ref "P7") (pin "2") (pinfunction "2_2") (pintype "passive"))
      (node (ref "P9") (pin "1") (pinfunction "1_1") (pintype "passive"))
      (node (ref "R19") (pin "2") (pinfunction "2_2") (pintype "passive"))
      (node (ref "R20") (pin "2") (pinfunction "2_2") (pintype "passive"))
      (node (ref "R3") (pin "1") (pinfunction "1_1") (pintype "passive"))
      (node (ref "U1") (pin "13") (pinfunction "VDDA_13") (pintype "passive"))
      (node (ref "U1") (pin "19") (pinfunction "VDD_4_19") (pintype "passive"))
      (node (ref "U1") (pin "32") (pinfunction "VDD_1_32") (pintype "passive"))
      (node (ref "U1") (pin "48") (pinfunction "VDD_2_48") (pintype "passive"))
      (node (ref "U1") (pin "64") (pinfunction "VDD_3_64") (pintype "passive"))
      (node (ref "U7") (pin "2") (pinfunction "OUT_2") (pintype "passive"))
      (node (ref "U8") (pin "8") (pinfunction "VDD_8") (pintype "passive"))
    )
    (net (code "53") (name "5V") (class "Default")
      (node (ref "C3") (pin "1") (pinfunction "1_1") (pintype "passive"))
      (node (ref "C4") (pin "2") (pinfunction "2_2") (pintype "passive"))
      (node (ref "CB1") (pin "2") (pinfunction "2_2") (pintype "passive"))
      (node (ref "J2") (pin "1") (pinfunction "1_1") (pintype "passive"))
      (node (ref "J3") (pin "1") (pinfunction "1_1") (pintype "passive"))
      (node (ref "P11") (pin "1") (pinfunction "1_1") (pintype "passive"))
      (node (ref "R1") (pin "2") (pinfunction "2_2") (pintype "passive"))
      (node (ref "U6") (pin "3") (pinfunction "OUT_3") (pintype "power_in"))
      (node (ref "U7") (pin "3") (pinfunction "IN_3") (pintype "passive"))
    )
    (net (code "54") (name "GND") (class "Default")
      (node (ref "BT1") (pin "2") (pinfunction "-_2") (pintype "passive"))
      (node (ref "C1") (pin "2") (pinfunction "2_2") (pintype "passive"))
      (node (ref "C10") (pin "2") (pinfunction "2_2") (pintype "passive"))
      (node (ref "C11") (pin "2") (pinfunction "2_2") (pintype "passive"))
      (node (ref "C12") (pin "2") (pinfunction "2_2") (pintype "passive"))
      (node (ref "C13") (pin "2") (pinfunction "2_2") (pintype "passive"))
      (node (ref "C14") (pin "1") (pinfunction "1_1") (pintype "passive"))
      (node (ref "C15") (pin "1") (pinfunction "1_1") (pintype "passive"))
      (node (ref "C16") (pin "2") (pinfunction "2_2") (pintype "passive"))
      (node (ref "C17") (pin "1") (pinfunction "1_1") (pintype "passive"))
      (node (ref "C18") (pin "1") (pinfunction "1_1") (pintype "passive"))
      (node (ref "C19") (pin "1") (pinfunction "1_1") (pintype "passive"))
      (node (ref "C2") (pin "1") (pinfunction "1_1") (pintype "passive"))
      (node (ref "C20") (pin "1") (pinfunction "1_1") (pintype "passive"))
      (node (ref "C21") (pin "1") (pinfunction "1_1") (pintype "passive"))
      (node (ref "C22") (pin "2") (pinfunction "2_2") (pintype "passive"))
      (node (ref "C23") (pin "2") (pinfunction "2_2") (pintype "passive"))
      (node (ref "C24") (pin "1") (pinfunction "1_1") (pintype "passive"))
      (node (ref "C25") (pin "1") (pinfunction "1_1") (pintype "passive"))
      (node (ref "C3") (pin "2") (pinfunction "2_2") (pintype "passive"))
      (node (ref "C4") (pin "1") (pinfunction "1_1") (pintype "passive"))
      (node (ref "C5") (pin "1") (pinfunction "1_1") (pintype "passive"))
      (node (ref "C6") (pin "1") (pinfunction "1_1") (pintype "passive"))
      (node (ref "C7") (pin "2") (pinfunction "2_2") (pintype "passive"))
      (node (ref "C8") (pin "1") (pinfunction "1_1") (pintype "passive"))
      (node (ref "C9") (pin "1") (pinfunction "1_1") (pintype "passive"))
      (node (ref "J1") (pin "2") (pinfunction "2_2") (pintype "passive"))
      (node (ref "J2") (pin "2") (pinfunction "2_2") (pintype "passive"))
      (node (ref "J3") (pin "2") (pinfunction "2_2") (pintype "passive"))
      (node (ref "LD1") (pin "2") (pintype "passive"))
      (node (ref "P1") (pin "3") (pinfunction "3_3") (pintype "passive"))
      (node (ref "P1") (pin "4") (pinfunction "4_4") (pintype "passive"))
      (node (ref "P10") (pin "4") (pinfunction "4_4") (pintype "passive"))
      (node (ref "P10") (pin "5") (pinfunction "5_5") (pintype "passive"))
      (node (ref "P11") (pin "2") (pinfunction "2_2") (pintype "passive"))
      (node (ref "P2") (pin "2") (pinfunction "2_2") (pintype "passive"))
      (node (ref "P3") (pin "1") (pinfunction "1_1") (pintype "passive"))
      (node (ref "P4") (pin "1") (pinfunction "1_1") (pintype "passive"))
      (node (ref "P5") (pin "1") (pinfunction "1_1") (pintype "passive"))
      (node (ref "P6") (pin "1") (pinfunction "1_1") (pintype "passive"))
      (node (ref "P7") (pin "1") (pinfunction "1_1") (pintype "passive"))
      (node (ref "P9") (pin "3") (pinfunction "3_3") (pintype "passive"))
      (node (ref "R18") (pin "1") (pinfunction "1_1") (pintype "passive"))
      (node (ref "S2") (pin "1") (pinfunction "1_1") (pintype "passive"))
      (node (ref "S3") (pin "1") (pinfunction "1_1") (pintype "passive"))
      (node (ref "S4") (pin "1") (pinfunction "1_1") (pintype "passive"))
      (node (ref "U1") (pin "12") (pinfunction "VSSA_12") (pintype "passive"))
      (node (ref "U1") (pin "18") (pinfunction "VSS_4_18") (pintype "passive"))
      (node (ref "U1") (pin "31") (pinfunction "VSS_1_31") (pintype "passive"))
      (node (ref "U1") (pin "47") (pinfunction "VSS_2_47") (pintype "passive"))
      (node (ref "U1") (pin "63") (pinfunction "VSS_3_63") (pintype "passive"))
      (node (ref "U2") (pin "4") (pinfunction "GND_4") (pintype "power_in"))
      (node (ref "U3") (pin "4") (pinfunction "GND_4") (pintype "power_in"))
      (node (ref "U4") (pin "4") (pinfunction "GND_4") (pintype "power_in"))
      (node (ref "U5") (pin "4") (pinfunction "GND_4") (pintype "power_in"))
      (node (ref "U6") (pin "2") (pinfunction "GND_2") (pintype "power_in"))
      (node (ref "U7") (pin "1") (pinfunction "GND_1") (pintype "passive"))
      (node (ref "U8") (pin "5") (pinfunction "GND_5") (pintype "passive"))
    )
    (net (code "55") (name "Net-(BT1-+)") (class "Default")
      (node (ref "BT1") (pin "1") (pinfunction "+_1") (pintype "passive"))
      (node (ref "JP1") (pin "1") (pinfunction "1_1") (pintype "passive"))
      (node (ref "U1") (pin "1") (pinfunction "VBAT_1") (pintype "passive"))
    )
    (net (code "56") (name "Net-(CB1-Pad1)") (class "Default")
      (node (ref "CB1") (pin "1") (pinfunction "1_1") (pintype "passive"))
      (node (ref "CB2") (pin "1") (pinfunction "1_1") (pintype "passive"))
      (node (ref "P3") (pin "4") (pinfunction "4_4") (pintype "passive"))
      (node (ref "P4") (pin "4") (pinfunction "4_4") (pintype "passive"))
      (node (ref "P5") (pin "4") (pinfunction "4_4") (pintype "passive"))
      (node (ref "P6") (pin "4") (pinfunction "4_4") (pintype "passive"))
    )
    (net (code "57") (name "Net-(LD1-Pad1)") (class "Default")
      (node (ref "LD1") (pin "1") (pintype "passive"))
      (node (ref "R1") (pin "1") (pinfunction "1_1") (pintype "passive"))
    )
    (net (code "58") (name "Net-(LD2-Pad1)") (class "Default")
      (node (ref "LD2") (pin "1") (pintype "passive"))
      (node (ref "R19") (pin "1") (pinfunction "1_1") (pintype "passive"))
    )
    (net (code "59") (name "Net-(LD3-Pad1)") (class "Default")
      (node (ref "LD3") (pin "1") (pintype "passive"))
      (node (ref "R20") (pin "1") (pinfunction "1_1") (pintype "passive"))
    )
    (net (code "60") (name "Net-(P1-Pad1)") (class "Default")
      (node (ref "P1") (pin "1") (pinfunction "1_1") (pintype "passive"))
      (node (ref "R2") (pin "2") (pinfunction "2_2") (pintype "passive"))
    )
    (net (code "61") (name "Net-(P1-Pad2)") (class "Default")
      (node (ref "P1") (pin "2") (pinfunction "2_2") (pintype "passive"))
      (node (ref "R5") (pin "1") (pinfunction "1_1") (pintype "passive"))
    )
    (net (code "62") (name "Net-(P1-Pad6)") (class "Default")
      (node (ref "P1") (pin "6") (pinfunction "6_6") (pintype "passive"))
      (node (ref "R6") (pin "1") (pinfunction "1_1") (pintype "passive"))
    )
    (net (code "63") (name "Net-(P1-Pad7)") (class "Default")
      (node (ref "P1") (pin "7") (pinfunction "7_7") (pintype "passive"))
      (node (ref "R3") (pin "2") (pinfunction "2_2") (pintype "passive"))
    )
    (net (code "64") (name "Net-(P1-Pad8)") (class "Default")
      (node (ref "P1") (pin "8") (pinfunction "8_8") (pintype "passive"))
      (node (ref "R7") (pin "1") (pinfunction "1_1") (pintype "passive"))
    )
    (net (code "65") (name "Net-(P1-Pad9)") (class "Default")
      (node (ref "P1") (pin "9") (pinfunction "9_9") (pintype "passive"))
      (node (ref "R4") (pin "2") (pinfunction "2_2") (pintype "passive"))
    )
    (net (code "66") (name "Net-(P1-Pad10)") (class "Default")
      (node (ref "P1") (pin "10") (pinfunction "10_10") (pintype "passive"))
      (node (ref "R8") (pin "1") (pinfunction "1_1") (pintype "passive"))
    )
    (net (code "67") (name "Net-(P3-Pad2)") (class "Default")
      (node (ref "P3") (pin "2") (pinfunction "2_2") (pintype "passive"))
      (node (ref "R9") (pin "1") (pinfunction "1_1") (pintype "passive"))
    )
    (net (code "68") (name "Net-(P3-Pad3)") (class "Default")
      (node (ref "P3") (pin "3") (pinfunction "3_3") (pintype "passive"))
      (node (ref "R10") (pin "1") (pinfunction "1_1") (pintype "passive"))
    )
    (net (code "69") (name "Net-(P4-Pad2)") (class "Default")
      (node (ref "P4") (pin "2") (pinfunction "2_2") (pintype "passive"))
      (node (ref "R11") (pin "1") (pinfunction "1_1") (pintype "passive"))
    )
    (net (code "70") (name "Net-(P4-Pad3)") (class "Default")
      (node (ref "P4") (pin "3") (pinfunction "3_3") (pintype "passive"))
      (node (ref "R12") (pin "1") (pinfunction "1_1") (pintype "passive"))
    )
    (net (code "71") (name "Net-(P5-Pad2)") (class "Default")
      (node (ref "P5") (pin "2") (pinfunction "2_2") (pintype "passive"))
      (node (ref "R13") (pin "1") (pinfunction "1_1") (pintype "passive"))
    )
    (net (code "72") (name "Net-(P5-Pad3)") (class "Default")
      (node (ref "P5") (pin "3") (pinfunction "3_3") (pintype "passive"))
      (node (ref "R14") (pin "1") (pinfunction "1_1") (pintype "passive"))
    )
    (net (code "73") (name "Net-(P6-Pad2)") (class "Default")
      (node (ref "P6") (pin "2") (pinfunction "2_2") (pintype "passive"))
      (node (ref "R15") (pin "1") (pinfunction "1_1") (pintype "passive"))
    )
    (net (code "74") (name "Net-(P6-Pad3)") (class "Default")
      (node (ref "P6") (pin "3") (pinfunction "3_3") (pintype "passive"))
      (node (ref "R16") (pin "1") (pinfunction "1_1") (pintype "passive"))
    )
    (net (code "75") (name "Net-(P8-Pad2)") (class "Default")
      (node (ref "P8") (pin "2") (pinfunction "2_2") (pintype "passive"))
      (node (ref "R9") (pin "2") (pinfunction "2_2") (pintype "passive"))
    )
    (net (code "76") (name "Net-(P8-Pad4)") (class "Default")
      (node (ref "P8") (pin "4") (pinfunction "4_4") (pintype "passive"))
      (node (ref "R10") (pin "2") (pinfunction "2_2") (pintype "passive"))
    )
    (net (code "77") (name "Net-(P8-Pad18)") (class "Default")
      (node (ref "P8") (pin "18") (pinfunction "18_18") (pintype "passive"))
      (node (ref "R11") (pin "2") (pinfunction "2_2") (pintype "passive"))
    )
    (net (code "78") (name "Net-(P8-Pad20)") (class "Default")
      (node (ref "P8") (pin "20") (pinfunction "20_20") (pintype "passive"))
      (node (ref "R12") (pin "2") (pinfunction "2_2") (pintype "passive"))
    )
    (net (code "79") (name "Net-(P8-Pad30)") (class "Default")
      (node (ref "P8") (pin "30") (pinfunction "30_30") (pintype "passive"))
      (node (ref "R13") (pin "2") (pinfunction "2_2") (pintype "passive"))
    )
    (net (code "80") (name "Net-(P8-Pad32)") (class "Default")
      (node (ref "P8") (pin "32") (pinfunction "32_32") (pintype "passive"))
      (node (ref "R14") (pin "2") (pinfunction "2_2") (pintype "passive"))
    )
    (net (code "81") (name "Net-(P8-Pad38)") (class "Default")
      (node (ref "P8") (pin "38") (pinfunction "38_38") (pintype "passive"))
      (node (ref "R16") (pin "2") (pinfunction "2_2") (pintype "passive"))
    )
    (net (code "82") (name "Net-(P8-Pad40)") (class "Default")
      (node (ref "P8") (pin "40") (pinfunction "40_40") (pintype "passive"))
      (node (ref "R15") (pin "2") (pinfunction "2_2") (pintype "passive"))
    )
    (net (code "83") (name "Net-(S1-COMMON)") (class "Default")
      (node (ref "F1") (pin "2") (pinfunction "2_2") (pintype "passive"))
      (node (ref "S1") (pin "1") (pinfunction "COMMON_1") (pintype "passive"))
    )
    (net (code "84") (name "Net-(U1-PC14{slash}OS32)") (class "Default")
      (node (ref "C8") (pin "2") (pinfunction "2_2") (pintype "passive"))
      (node (ref "U1") (pin "3") (pinfunction "PC14/OS32_3") (pintype "passive"))
      (node (ref "Y1") (pin "2") (pinfunction "2_2") (pintype "passive"))
    )
    (net (code "85") (name "Net-(U1-PC15{slash}OS32)") (class "Default")
      (node (ref "C9") (pin "2") (pinfunction "2_2") (pintype "passive"))
      (node (ref "U1") (pin "4") (pinfunction "PC15/OS32_4") (pintype "passive"))
      (node (ref "Y1") (pin "1") (pinfunction "1_1") (pintype "passive"))
    )
    (net (code "86") (name "Net-(U1-PD0{slash}OSC_IN)") (class "Default")
      (node (ref "C10") (pin "1") (pinfunction "1_1") (pintype "passive"))
      (node (ref "U1") (pin "5") (pinfunction "PD0/OSC_IN_5") (pintype "passive"))
      (node (ref "Y2") (pin "1") (pinfunction "1_1") (pintype "passive"))
    )
    (net (code "87") (name "Net-(U1-PD1{slash}OSC_OUT)") (class "Default")
      (node (ref "C11") (pin "1") (pinfunction "1_1") (pintype "passive"))
      (node (ref "U1") (pin "6") (pinfunction "PD1/OSC_OUT_6") (pintype "passive"))
      (node (ref "Y2") (pin "2") (pinfunction "2_2") (pintype "passive"))
    )
    (net (code "88") (name "Net-(U2-EF)") (class "Default")
      (node (ref "P8") (pin "16") (pinfunction "16_16") (pintype "passive"))
      (node (ref "U2") (pin "2") (pinfunction "EF_2") (pintype "open_collector"))
    )
    (net (code "89") (name "Net-(U2-IN1)") (class "Default")
      (node (ref "P8") (pin "14") (pinfunction "14_14") (pintype "passive"))
      (node (ref "U2") (pin "3") (pinfunction "IN1_3") (pintype "input"))
    )
    (net (code "90") (name "Net-(U2-IN2)") (class "Default")
      (node (ref "P8") (pin "6") (pinfunction "6_6") (pintype "passive"))
      (node (ref "U2") (pin "5") (pinfunction "IN2_5") (pintype "input"))
    )
    (net (code "91") (name "Net-(U2-OUT1)") (class "Default")
      (node (ref "JP2") (pin "1") (pinfunction "1_1") (pintype "passive"))
      (node (ref "U2") (pin "1") (pinfunction "OUT1_1") (pintype "power_in"))
    )
    (net (code "92") (name "Net-(U2-OUT2)") (class "Default")
      (node (ref "JP2") (pin "2") (pinfunction "2_2") (pintype "passive"))
      (node (ref "U2") (pin "7") (pinfunction "OUT2_7") (pintype "power_in"))
    )
    (net (code "93") (name "Net-(U3-EF)") (class "Default")
      (node (ref "P8") (pin "24") (pinfunction "24_24") (pintype "passive"))
      (node (ref "U3") (pin "2") (pinfunction "EF_2") (pintype "open_collector"))
    )
    (net (code "94") (name "Net-(U3-IN1)") (class "Default")
      (node (ref "P8") (pin "22") (pinfunction "22_22") (pintype "passive"))
      (node (ref "U3") (pin "3") (pinfunction "IN1_3") (pintype "input"))
    )
    (net (code "95") (name "Net-(U3-IN2)") (class "Default")
      (node (ref "P8") (pin "8") (pinfunction "8_8") (pintype "passive"))
      (node (ref "U3") (pin "5") (pinfunction "IN2_5") (pintype "input"))
    )
    (net (code "96") (name "Net-(U3-OUT1)") (class "Default")
      (node (ref "JP3") (pin "1") (pinfunction "1_1") (pintype "passive"))
      (node (ref "U3") (pin "1") (pinfunction "OUT1_1") (pintype "power_in"))
    )
    (net (code "97") (name "Net-(U3-OUT2)") (class "Default")
      (node (ref "JP3") (pin "2") (pinfunction "2_2") (pintype "passive"))
      (node (ref "U3") (pin "7") (pinfunction "OUT2_7") (pintype "power_in"))
    )
    (net (code "98") (name "Net-(U4-EF)") (class "Default")
      (node (ref "P8") (pin "28") (pinfunction "28_28") (pintype "passive"))
      (node (ref "U4") (pin "2") (pinfunction "EF_2") (pintype "open_collector"))
    )
    (net (code "99") (name "Net-(U4-IN1)") (class "Default")
      (node (ref "P8") (pin "26") (pinfunction "26_26") (pintype "passive"))
      (node (ref "U4") (pin "3") (pinfunction "IN1_3") (pintype "input"))
    )
    (net (code "100") (name "Net-(U4-IN2)") (class "Default")
      (node (ref "P8") (pin "10") (pinfunction "10_10") (pintype "passive"))
      (node (ref "U4") (pin "5") (pinfunction "IN2_5") (pintype "input"))
    )
    (net (code "101") (name "Net-(U4-OUT1)") (class "Default")
      (node (ref "JP4") (pin "1") (pinfunction "1_1") (pintype "passive"))
      (node (ref "U4") (pin "1") (pinfunction "OUT1_1") (pintype "power_in"))
    )
    (net (code "102") (name "Net-(U4-OUT2)") (class "Default")
      (node (ref "JP4") (pin "2") (pinfunction "2_2") (pintype "passive"))
      (node (ref "U4") (pin "7") (pinfunction "OUT2_7") (pintype "power_in"))
    )
    (net (code "103") (name "Net-(U5-EF)") (class "Default")
      (node (ref "P8") (pin "36") (pinfunction "36_36") (pintype "passive"))
      (node (ref "U5") (pin "2") (pinfunction "EF_2") (pintype "open_collector"))
    )
    (net (code "104") (name "Net-(U5-IN1)") (class "Default")
      (node (ref "P8") (pin "34") (pinfunction "34_34") (pintype "passive"))
      (node (ref "U5") (pin "3") (pinfunction "IN1_3") (pintype "input"))
    )
    (net (code "105") (name "Net-(U5-IN2)") (class "Default")
      (node (ref "P8") (pin "12") (pinfunction "12_12") (pintype "passive"))
      (node (ref "U5") (pin "5") (pinfunction "IN2_5") (pintype "input"))
    )
    (net (code "106") (name "Net-(U5-OUT1)") (class "Default")
      (node (ref "JP5") (pin "1") (pinfunction "1_1") (pintype "passive"))
      (node (ref "U5") (pin "1") (pinfunction "OUT1_1") (pintype "power_in"))
    )
    (net (code "107") (name "Net-(U5-OUT2)") (class "Default")
      (node (ref "JP5") (pin "2") (pinfunction "2_2") (pintype "passive"))
      (node (ref "U5") (pin "7") (pinfunction "OUT2_7") (pintype "power_in"))
    )
    (net (code "108") (name "Vbat") (class "Default")
      (node (ref "J1") (pin "1") (pinfunction "1_1") (pintype "passive"))
      (node (ref "S1") (pin "2") (pinfunction "NO_2") (pintype "passive"))
    )
    (net (code "109") (name "Vss") (class "Default")
      (node (ref "C1") (pin "1") (pinfunction "1_1") (pintype "passive"))
      (node (ref "C18") (pin "2") (pinfunction "2_2") (pintype "passive"))
      (node (ref "C19") (pin "2") (pinfunction "2_2") (pintype "passive"))
      (node (ref "C2") (pin "2") (pinfunction "2_2") (pintype "passive"))
      (node (ref "C20") (pin "2") (pinfunction "2_2") (pintype "passive"))
      (node (ref "C21") (pin "2") (pinfunction "2_2") (pintype "passive"))
      (node (ref "F1") (pin "1") (pinfunction "1_1") (pintype "passive"))
      (node (ref "R17") (pin "2") (pinfunction "2_2") (pintype "passive"))
      (node (ref "U2") (pin "6") (pinfunction "VS_6") (pintype "power_in"))
      (node (ref "U3") (pin "6") (pinfunction "VS_6") (pintype "power_in"))
      (node (ref "U4") (pin "6") (pinfunction "VS_6") (pintype "power_in"))
      (node (ref "U5") (pin "6") (pinfunction "VS_6") (pintype "power_in"))
      (node (ref "U6") (pin "1") (pinfunction "IN_1") (pintype "power_in"))
    )
    (net (code "110") (name "unconnected-(P1-Pad5)") (class "Default")
      (node (ref "P1") (pin "5") (pinfunction "5_5") (pintype "passive"))
    )
    (net (code "111") (name "unconnected-(P2-Pad5)") (class "Default")
      (node (ref "P2") (pin "5") (pinfunction "5_5") (pintype "passive"))
    )
    (net (code "112") (name "unconnected-(P2-Pad6)") (class "Default")
      (node (ref "P2") (pin "6") (pinfunction "6_6") (pintype "passive"))
    )
    (net (code "113") (name "unconnected-(P2-Pad9)") (class "Default")
      (node (ref "P2") (pin "9") (pinfunction "9_9") (pintype "passive"))
    )
    (net (code "114") (name "unconnected-(P2-Pad10)") (class "Default")
      (node (ref "P2") (pin "10") (pinfunction "10_10") (pintype "passive"))
    )
  )
)
